# SESBOARD.net
KiCad netlist of a schematic drawn in EasyEDA
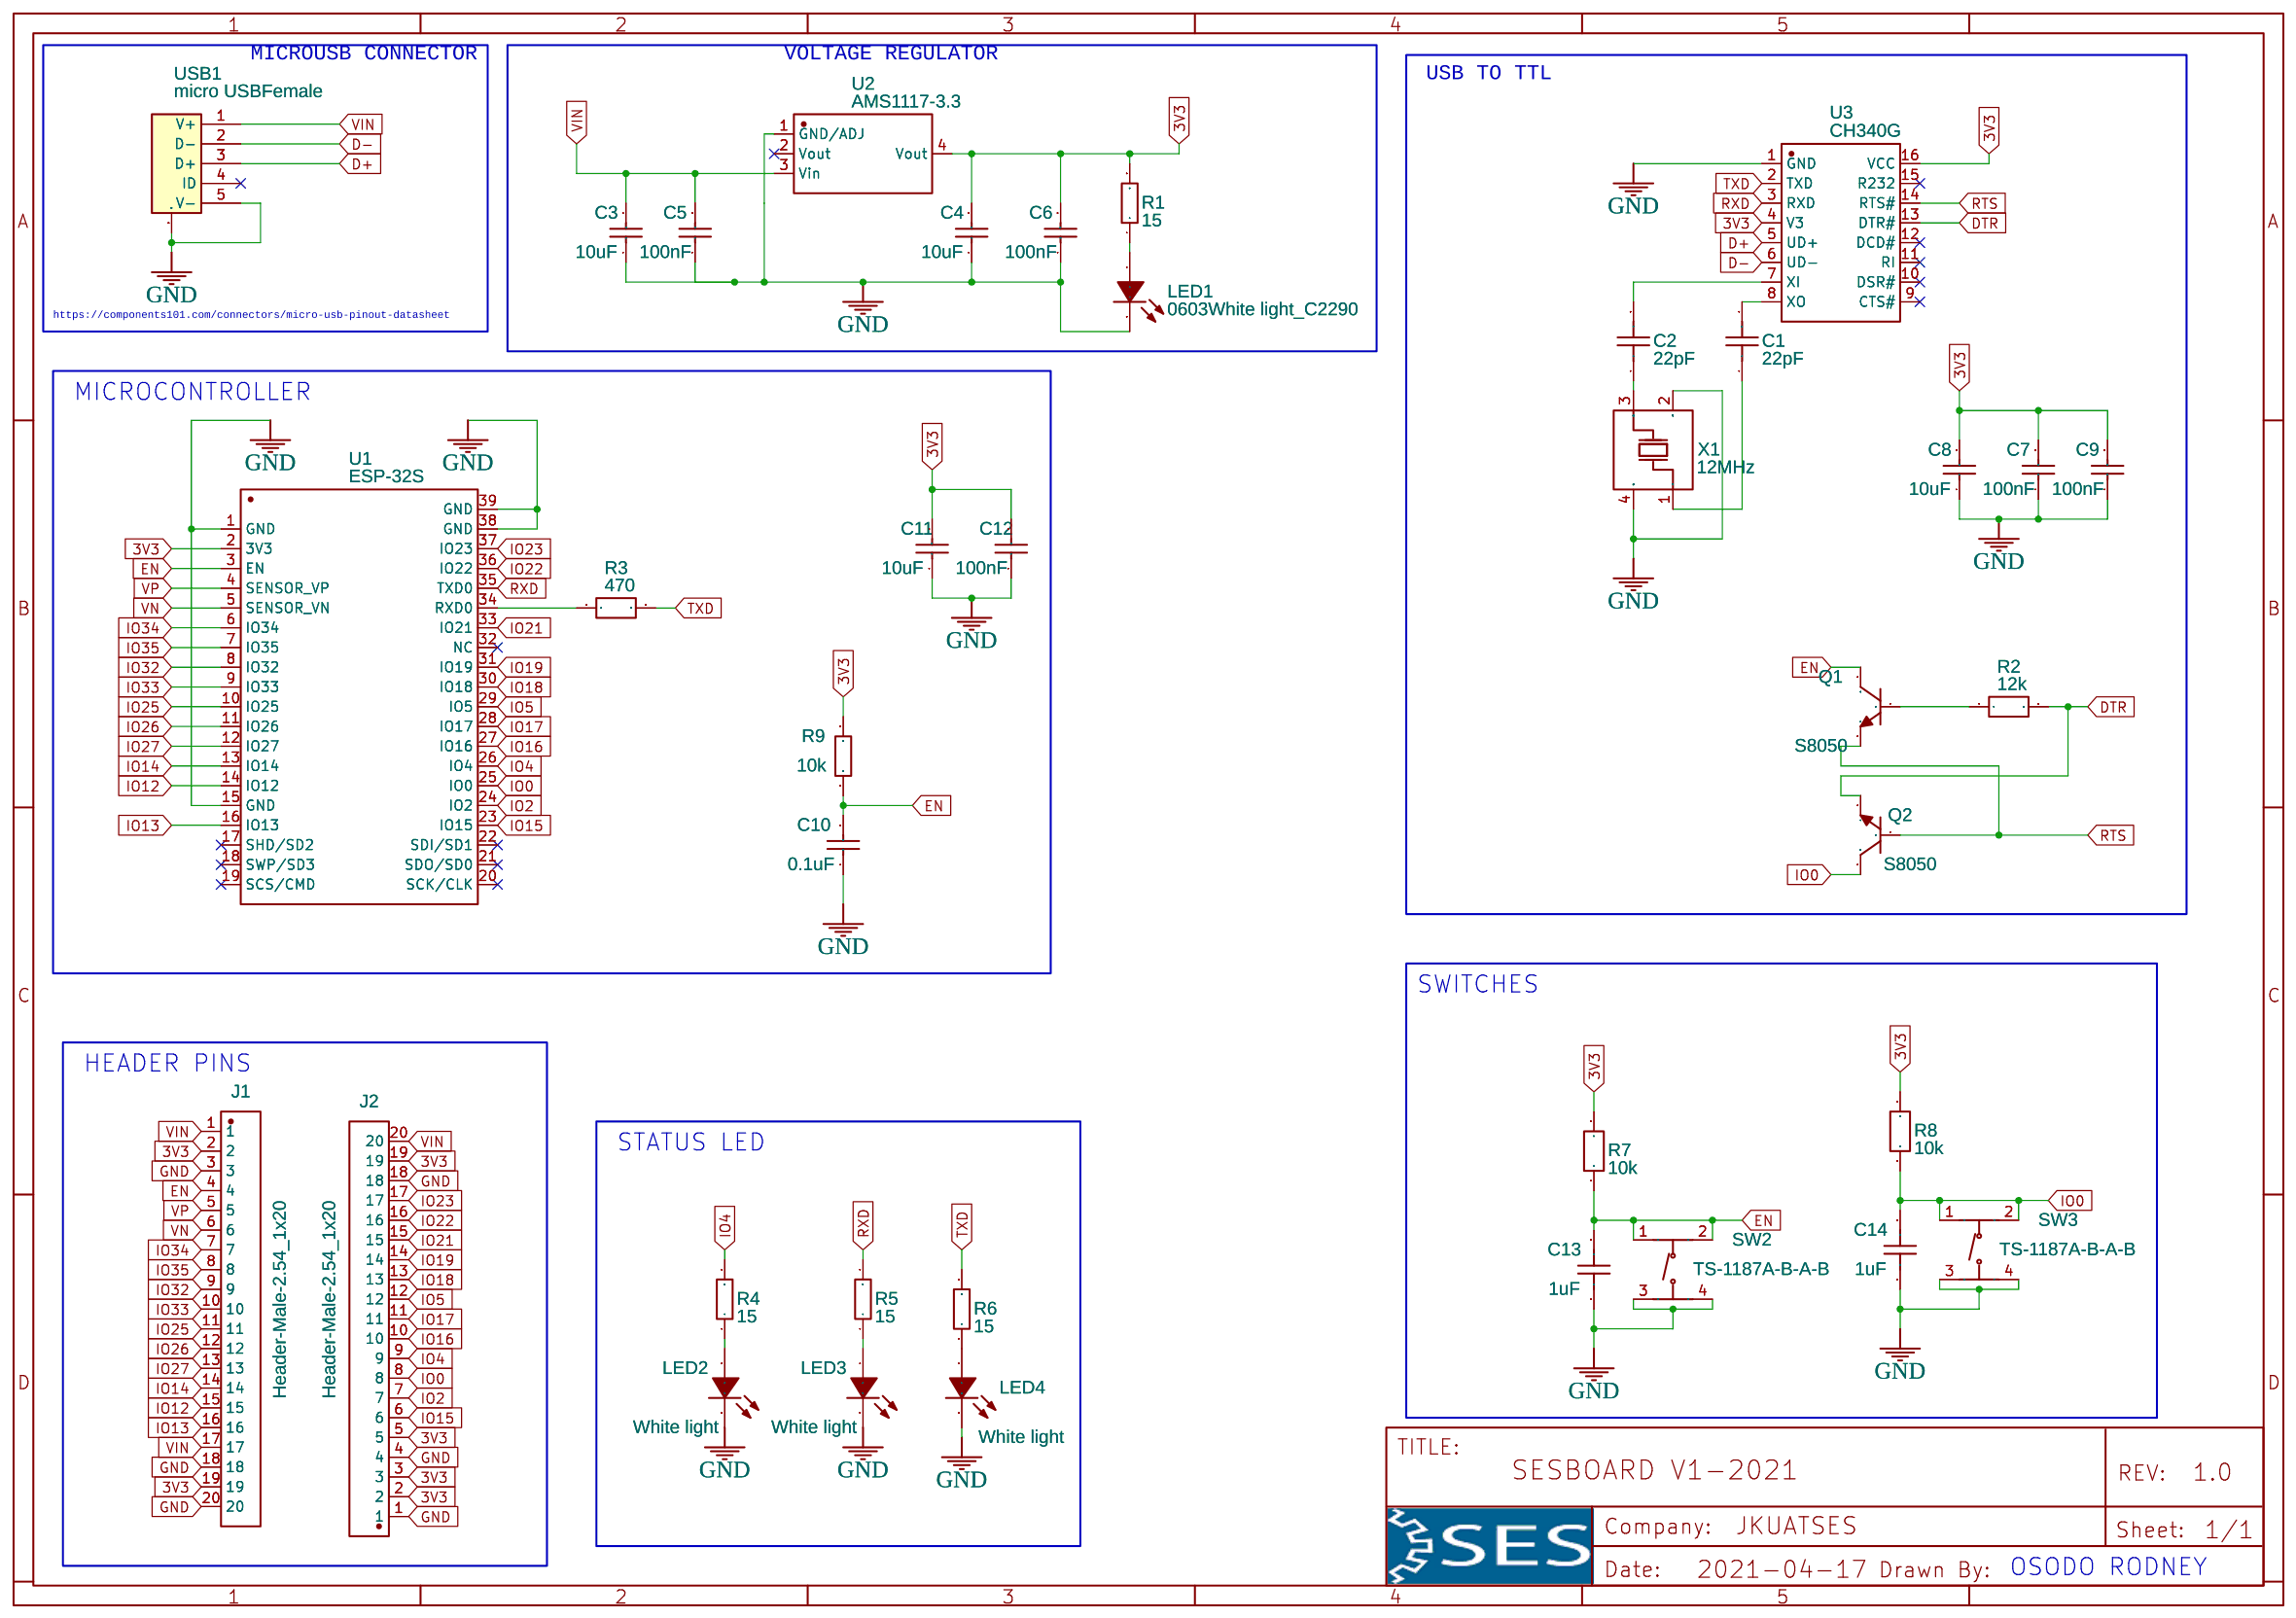
[diagram p0: schematic sheet]

(export (version "E")
  (design (tool "Eeschema 10.0.6"))
  (components
    (comp (ref "C1")
      (value "22pF")
      (fields
        (field (name "BOM_Manufacturer Part") "TCC0805COG220J500BT")
        (field (name "BOM_Supplier Part") "C376875")
      )
      (libsource (lib "") (part "TCC0805COG220J500BT"))
    )
    (comp (ref "C2")
      (value "22pF")
      (fields
        (field (name "BOM_Manufacturer Part") "TCC0805COG220J500BT")
        (field (name "BOM_Supplier Part") "C376875")
      )
      (libsource (lib "") (part "TCC0805COG220J500BT"))
    )
    (comp (ref "C3")
      (value "10uF")
      (fields
        (field (name "BOM_Manufacturer Part") "CL21A106KPFNNNE")
        (field (name "BOM_Supplier Part") "C17024")
      )
      (libsource (lib "") (part "CL21A106KPFNNNE"))
    )
    (comp (ref "C4")
      (value "10uF")
      (fields
        (field (name "BOM_Manufacturer Part") "CL21A106KPFNNNE")
        (field (name "BOM_Supplier Part") "C17024")
      )
      (libsource (lib "") (part "CL21A106KPFNNNE"))
    )
    (comp (ref "C5")
      (value "100nF")
      (fields
        (field (name "BOM_Manufacturer Part") "CL21F104ZBCNNNC")
        (field (name "BOM_Supplier Part") "C1760")
      )
      (libsource (lib "") (part "CL21F104ZBCNNNC"))
    )
    (comp (ref "C6")
      (value "100nF")
      (fields
        (field (name "BOM_Manufacturer Part") "CL21F104ZBCNNNC")
        (field (name "BOM_Supplier Part") "C1760")
      )
      (libsource (lib "") (part "CL21F104ZBCNNNC"))
    )
    (comp (ref "C7")
      (value "100nF")
      (fields
        (field (name "BOM_Manufacturer Part") "CL21F104ZBCNNNC")
        (field (name "BOM_Supplier Part") "C1760")
      )
      (libsource (lib "") (part "CL21F104ZBCNNNC"))
    )
    (comp (ref "C8")
      (value "10uF")
      (fields
        (field (name "BOM_Manufacturer Part") "CL21A106KPFNNNE")
        (field (name "BOM_Supplier Part") "C17024")
      )
      (libsource (lib "") (part "CL21A106KPFNNNE"))
    )
    (comp (ref "C9")
      (value "100nF")
      (fields
        (field (name "BOM_Manufacturer Part") "CL21F104ZBCNNNC")
        (field (name "BOM_Supplier Part") "C1760")
      )
      (libsource (lib "") (part "CL21F104ZBCNNNC"))
    )
    (comp (ref "C10")
      (value "0.1uF")
      (fields
        (field (name "BOM_Manufacturer Part") "CL21F104ZBCNNNC")
        (field (name "BOM_Supplier Part") "C1760")
      )
      (libsource (lib "") (part "CL21F104ZBCNNNC"))
    )
    (comp (ref "C11")
      (value "10uF")
      (fields
        (field (name "BOM_Manufacturer Part") "CL21A106KPFNNNE")
        (field (name "BOM_Supplier Part") "C17024")
      )
      (libsource (lib "") (part "CL21A106KPFNNNE"))
    )
    (comp (ref "C12")
      (value "100nF")
      (fields
        (field (name "BOM_Manufacturer Part") "CL21F104ZBCNNNC")
        (field (name "BOM_Supplier Part") "C1760")
      )
      (libsource (lib "") (part "CL21F104ZBCNNNC"))
    )
    (comp (ref "C13") (value "1uF") (libsource (lib "") (part "C_0603_US")))
    (comp (ref "C14") (value "1uF") (libsource (lib "") (part "C_0603_US")))
    (comp (ref "J1")
      (value "Header-Male-2.54_1x20")
      (fields
        (field (name "BOM_Manufacturer Part") "2.54mm 1*20PHeader")
        (field (name "BOM_Supplier Part") "C50981")
      )
      (libsource (lib "") (part "Header-Male-2.54_1x20_1"))
    )
    (comp (ref "J2")
      (value "Header-Male-2.54_1x20")
      (fields
        (field (name "BOM_Manufacturer Part") "2.54mm 1*20PHeader")
        (field (name "BOM_Supplier Part") "C50981")
      )
      (libsource (lib "") (part "Header-Male-2.54_1x20"))
    )
    (comp (ref "LED1")
      (value "0603White light_C2290")
      (fields
        (field (name "BOM_Manufacturer Part") "0603White light")
        (field (name "BOM_Supplier Part") "C2290")
      )
      (libsource (lib "") (part "0603White light_C2290"))
    )
    (comp (ref "LED2")
      (value "White light")
      (fields
        (field (name "BOM_Manufacturer Part") "0603White light")
        (field (name "BOM_Supplier Part") "C2290")
      )
      (libsource (lib "") (part "0603White light_C2290"))
    )
    (comp (ref "LED3")
      (value "White light")
      (fields
        (field (name "BOM_Manufacturer Part") "0603White light")
        (field (name "BOM_Supplier Part") "C2290")
      )
      (libsource (lib "") (part "0603White light_C2290"))
    )
    (comp (ref "LED4")
      (value "White light")
      (fields
        (field (name "BOM_Manufacturer Part") "0603White light")
        (field (name "BOM_Supplier Part") "C2290")
      )
      (libsource (lib "") (part "0603White light_C2290"))
    )
    (comp (ref "Q1")
      (value "S8050")
      (fields (field (name "BOM_Supplier Part") "C909746"))
      (libsource (lib "") (part "S8050"))
    )
    (comp (ref "Q2")
      (value "S8050")
      (fields (field (name "BOM_Supplier Part") "C909746"))
      (libsource (lib "") (part "S8050_1"))
    )
    (comp (ref "R1")
      (value "15")
      (fields
        (field (name "BOM_Manufacturer Part") "0603WAF150JT5E")
        (field (name "BOM_Supplier Part") "C22810")
      )
      (libsource (lib "") (part "0603WAF150JT5E"))
    )
    (comp (ref "R2") (value "12k") (libsource (lib "") (part "R_0603_EU_1")))
    (comp (ref "R3") (value "470") (libsource (lib "") (part "R_0603_EU_1")))
    (comp (ref "R4")
      (value "15")
      (fields
        (field (name "BOM_Manufacturer Part") "0603WAF150JT5E")
        (field (name "BOM_Supplier Part") "C22810")
      )
      (libsource (lib "") (part "0603WAF150JT5E"))
    )
    (comp (ref "R5")
      (value "15")
      (fields
        (field (name "BOM_Manufacturer Part") "0603WAF150JT5E")
        (field (name "BOM_Supplier Part") "C22810")
      )
      (libsource (lib "") (part "0603WAF150JT5E"))
    )
    (comp (ref "R6")
      (value "15")
      (fields
        (field (name "BOM_Manufacturer Part") "0603WAF150JT5E")
        (field (name "BOM_Supplier Part") "C22810")
      )
      (libsource (lib "") (part "0603WAF150JT5E"))
    )
    (comp (ref "R7") (value "10k") (libsource (lib "") (part "R_0603_EU")))
    (comp (ref "R8") (value "10k") (libsource (lib "") (part "R_0603_EU")))
    (comp (ref "R9")
      (value "10k")
      (fields
        (field (name "BOM_Manufacturer Part") "0603WAF150JT5E")
        (field (name "BOM_Supplier Part") "C22810")
      )
      (libsource (lib "") (part "0603WAF150JT5E"))
    )
    (comp (ref "SW2")
      (value "TS-1187A-B-A-B")
      (fields (field (name "BOM_Supplier Part") "C318884"))
      (libsource (lib "") (part "TS-1187A-B-A-B"))
    )
    (comp (ref "SW3")
      (value "TS-1187A-B-A-B")
      (fields (field (name "BOM_Supplier Part") "C318884"))
      (libsource (lib "") (part "TS-1187A-B-A-B"))
    )
    (comp (ref "U1")
      (value "ESP-32S")
      (fields (field (name "BOM_Supplier Part") "C82899"))
      (libsource (lib "") (part "ESP-32S"))
    )
    (comp (ref "U2")
      (value "AMS1117-3.3")
      (fields (field (name "BOM_Supplier Part") "C6186"))
      (libsource (lib "") (part "AMS1117-3.3"))
    )
    (comp (ref "U3")
      (value "CH340G")
      (fields (field (name "BOM_Supplier Part") "C14267"))
      (libsource (lib "") (part "CH340G"))
    )
    (comp (ref "USB1")
      (value "micro USBFemale")
      (fields (field (name "BOM_Supplier Part") "C10418"))
      (libsource (lib "") (part "micro USBFemale"))
    )
    (comp (ref "X1")
      (value "12MHz")
      (fields
        (field (name "BOM_Manufacturer Part") "X322512MSB4SI")
        (field (name "BOM_Supplier Part") "C9002")
      )
      (libsource (lib "") (part "X322512MSB4SI"))
    )
  )
  (nets
    (net (code "1") (name "3V3") (class "Default")
      (node (ref "C11") (pin "2") (pinfunction "2_2") (pintype "input"))
      (node (ref "C12") (pin "2") (pinfunction "2_2") (pintype "input"))
      (node (ref "C4") (pin "2") (pinfunction "2_2") (pintype "input"))
      (node (ref "C6") (pin "2") (pinfunction "2_2") (pintype "input"))
      (node (ref "C7") (pin "2") (pinfunction "2_2") (pintype "input"))
      (node (ref "C8") (pin "2") (pinfunction "2_2") (pintype "input"))
      (node (ref "C9") (pin "2") (pinfunction "2_2") (pintype "input"))
      (node (ref "J1") (pin "19") (pinfunction "19_19") (pintype "unspecified"))
      (node (ref "J1") (pin "2") (pinfunction "2_2") (pintype "unspecified"))
      (node (ref "J2") (pin "19") (pinfunction "19_19") (pintype "unspecified"))
      (node (ref "J2") (pin "2") (pinfunction "2_2") (pintype "unspecified"))
      (node (ref "J2") (pin "3") (pinfunction "3_3") (pintype "unspecified"))
      (node (ref "J2") (pin "5") (pinfunction "5_5") (pintype "unspecified"))
      (node (ref "R1") (pin "2") (pinfunction "2_2") (pintype "input"))
      (node (ref "R7") (pin "2") (pinfunction "2_2") (pintype "unspecified"))
      (node (ref "R8") (pin "2") (pinfunction "2_2") (pintype "unspecified"))
      (node (ref "R9") (pin "2") (pinfunction "2_2") (pintype "input"))
      (node (ref "U1") (pin "2") (pinfunction "3V3_2") (pintype "unspecified"))
      (node (ref "U2") (pin "4") (pinfunction "Vout_4") (pintype "unspecified"))
      (node (ref "U3") (pin "16") (pinfunction "VCC_16") (pintype "unspecified"))
      (node (ref "U3") (pin "4") (pinfunction "V3_4") (pintype "unspecified"))
    )
    (net (code "2") (name "D+") (class "Default")
      (node (ref "U3") (pin "5") (pinfunction "UD+_5") (pintype "unspecified"))
      (node (ref "USB1") (pin "3") (pinfunction "D+_3") (pintype "unspecified"))
    )
    (net (code "3") (name "D-") (class "Default")
      (node (ref "U3") (pin "6") (pinfunction "UD-_6") (pintype "unspecified"))
      (node (ref "USB1") (pin "2") (pinfunction "D-_2") (pintype "unspecified"))
    )
    (net (code "4") (name "DTR") (class "Default")
      (node (ref "Q2") (pin "2") (pinfunction "E_2") (pintype "input"))
      (node (ref "R2") (pin "2") (pinfunction "2_2") (pintype "unspecified"))
      (node (ref "U3") (pin "13") (pinfunction "DTR#_13") (pintype "unspecified"))
    )
    (net (code "5") (name "EN") (class "Default")
      (node (ref "C10") (pin "2") (pinfunction "2_2") (pintype "input"))
      (node (ref "C13") (pin "2") (pinfunction "2_2") (pintype "unspecified"))
      (node (ref "J1") (pin "4") (pinfunction "4_4") (pintype "unspecified"))
      (node (ref "Q1") (pin "3") (pinfunction "C_3") (pintype "input"))
      (node (ref "R7") (pin "1") (pinfunction "1_1") (pintype "unspecified"))
      (node (ref "R9") (pin "1") (pinfunction "1_1") (pintype "input"))
      (node (ref "SW2") (pin "1") (pinfunction "A_1") (pintype "unspecified"))
      (node (ref "SW2") (pin "2") (pinfunction "B_2") (pintype "unspecified"))
      (node (ref "U1") (pin "3") (pinfunction "EN_3") (pintype "unspecified"))
    )
    (net (code "6") (name "GND") (class "Default")
      (node (ref "C10") (pin "1") (pinfunction "1_1") (pintype "input"))
      (node (ref "C11") (pin "1") (pinfunction "1_1") (pintype "input"))
      (node (ref "C12") (pin "1") (pinfunction "1_1") (pintype "input"))
      (node (ref "C13") (pin "1") (pinfunction "1_1") (pintype "unspecified"))
      (node (ref "C14") (pin "1") (pinfunction "1_1") (pintype "unspecified"))
      (node (ref "C3") (pin "1") (pinfunction "1_1") (pintype "input"))
      (node (ref "C4") (pin "1") (pinfunction "1_1") (pintype "input"))
      (node (ref "C5") (pin "1") (pinfunction "1_1") (pintype "input"))
      (node (ref "C6") (pin "1") (pinfunction "1_1") (pintype "input"))
      (node (ref "C7") (pin "1") (pinfunction "1_1") (pintype "input"))
      (node (ref "C8") (pin "1") (pinfunction "1_1") (pintype "input"))
      (node (ref "C9") (pin "1") (pinfunction "1_1") (pintype "input"))
      (node (ref "J1") (pin "18") (pinfunction "18_18") (pintype "unspecified"))
      (node (ref "J1") (pin "20") (pinfunction "20_20") (pintype "unspecified"))
      (node (ref "J1") (pin "3") (pinfunction "3_3") (pintype "unspecified"))
      (node (ref "J2") (pin "1") (pinfunction "1_1") (pintype "unspecified"))
      (node (ref "J2") (pin "18") (pinfunction "18_18") (pintype "unspecified"))
      (node (ref "J2") (pin "4") (pinfunction "4_4") (pintype "unspecified"))
      (node (ref "LED1") (pin "2") (pinfunction "K_2") (pintype "unspecified"))
      (node (ref "LED2") (pin "2") (pinfunction "K_2") (pintype "unspecified"))
      (node (ref "LED3") (pin "2") (pinfunction "K_2") (pintype "unspecified"))
      (node (ref "LED4") (pin "2") (pinfunction "K_2") (pintype "unspecified"))
      (node (ref "SW2") (pin "3") (pinfunction "C_3") (pintype "unspecified"))
      (node (ref "SW2") (pin "4") (pinfunction "D_4") (pintype "unspecified"))
      (node (ref "SW3") (pin "3") (pinfunction "C_3") (pintype "unspecified"))
      (node (ref "SW3") (pin "4") (pinfunction "D_4") (pintype "unspecified"))
      (node (ref "U1") (pin "1") (pinfunction "GND_1") (pintype "unspecified"))
      (node (ref "U1") (pin "15") (pinfunction "GND_15") (pintype "unspecified"))
      (node (ref "U1") (pin "38") (pinfunction "GND_38") (pintype "unspecified"))
      (node (ref "U1") (pin "39") (pinfunction "GND_39") (pintype "unspecified"))
      (node (ref "U2") (pin "1") (pinfunction "GND/ADJ_1") (pintype "unspecified"))
      (node (ref "U3") (pin "1") (pinfunction "GND_1") (pintype "unspecified"))
      (node (ref "USB1") (pin "0") (pinfunction "MTN_0") (pintype "input"))
      (node (ref "USB1") (pin "5") (pinfunction "V-_5") (pintype "unspecified"))
      (node (ref "X1") (pin "2") (pinfunction "GND_2") (pintype "unspecified"))
      (node (ref "X1") (pin "4") (pinfunction "GND_4") (pintype "unspecified"))
    )
    (net (code "7") (name "IO0") (class "Default")
      (node (ref "C14") (pin "2") (pinfunction "2_2") (pintype "unspecified"))
      (node (ref "J2") (pin "8") (pinfunction "8_8") (pintype "unspecified"))
      (node (ref "Q2") (pin "3") (pinfunction "C_3") (pintype "input"))
      (node (ref "R8") (pin "1") (pinfunction "1_1") (pintype "unspecified"))
      (node (ref "SW3") (pin "1") (pinfunction "A_1") (pintype "unspecified"))
      (node (ref "SW3") (pin "2") (pinfunction "B_2") (pintype "unspecified"))
      (node (ref "U1") (pin "25") (pinfunction "IO0_25") (pintype "unspecified"))
    )
    (net (code "8") (name "IO2") (class "Default")
      (node (ref "J2") (pin "7") (pinfunction "7_7") (pintype "unspecified"))
      (node (ref "U1") (pin "24") (pinfunction "IO2_24") (pintype "unspecified"))
    )
    (net (code "9") (name "IO4") (class "Default")
      (node (ref "J2") (pin "9") (pinfunction "9_9") (pintype "unspecified"))
      (node (ref "R4") (pin "2") (pinfunction "2_2") (pintype "input"))
      (node (ref "U1") (pin "26") (pinfunction "IO4_26") (pintype "unspecified"))
    )
    (net (code "10") (name "IO5") (class "Default")
      (node (ref "J2") (pin "12") (pinfunction "12_12") (pintype "unspecified"))
      (node (ref "U1") (pin "29") (pinfunction "IO5_29") (pintype "unspecified"))
    )
    (net (code "11") (name "IO12") (class "Default")
      (node (ref "J1") (pin "15") (pinfunction "15_15") (pintype "unspecified"))
      (node (ref "U1") (pin "14") (pinfunction "IO12_14") (pintype "unspecified"))
    )
    (net (code "12") (name "IO13") (class "Default")
      (node (ref "J1") (pin "16") (pinfunction "16_16") (pintype "unspecified"))
      (node (ref "U1") (pin "16") (pinfunction "IO13_16") (pintype "unspecified"))
    )
    (net (code "13") (name "IO14") (class "Default")
      (node (ref "J1") (pin "14") (pinfunction "14_14") (pintype "unspecified"))
      (node (ref "U1") (pin "13") (pinfunction "IO14_13") (pintype "unspecified"))
    )
    (net (code "14") (name "IO15") (class "Default")
      (node (ref "J2") (pin "6") (pinfunction "6_6") (pintype "unspecified"))
      (node (ref "U1") (pin "23") (pinfunction "IO15_23") (pintype "unspecified"))
    )
    (net (code "15") (name "IO16") (class "Default")
      (node (ref "J2") (pin "10") (pinfunction "10_10") (pintype "unspecified"))
      (node (ref "U1") (pin "27") (pinfunction "IO16_27") (pintype "unspecified"))
    )
    (net (code "16") (name "IO17") (class "Default")
      (node (ref "J2") (pin "11") (pinfunction "11_11") (pintype "unspecified"))
      (node (ref "U1") (pin "28") (pinfunction "IO17_28") (pintype "unspecified"))
    )
    (net (code "17") (name "IO18") (class "Default")
      (node (ref "J2") (pin "13") (pinfunction "13_13") (pintype "unspecified"))
      (node (ref "U1") (pin "30") (pinfunction "IO18_30") (pintype "unspecified"))
    )
    (net (code "18") (name "IO19") (class "Default")
      (node (ref "J2") (pin "14") (pinfunction "14_14") (pintype "unspecified"))
      (node (ref "U1") (pin "31") (pinfunction "IO19_31") (pintype "unspecified"))
    )
    (net (code "19") (name "IO21") (class "Default")
      (node (ref "J2") (pin "15") (pinfunction "15_15") (pintype "unspecified"))
      (node (ref "U1") (pin "33") (pinfunction "IO21_33") (pintype "unspecified"))
    )
    (net (code "20") (name "IO22") (class "Default")
      (node (ref "J2") (pin "16") (pinfunction "16_16") (pintype "unspecified"))
      (node (ref "U1") (pin "36") (pinfunction "IO22_36") (pintype "unspecified"))
    )
    (net (code "21") (name "IO23") (class "Default")
      (node (ref "J2") (pin "17") (pinfunction "17_17") (pintype "unspecified"))
      (node (ref "U1") (pin "37") (pinfunction "IO23_37") (pintype "unspecified"))
    )
    (net (code "22") (name "IO25") (class "Default")
      (node (ref "J1") (pin "11") (pinfunction "11_11") (pintype "unspecified"))
      (node (ref "U1") (pin "10") (pinfunction "IO25_10") (pintype "unspecified"))
    )
    (net (code "23") (name "IO26") (class "Default")
      (node (ref "J1") (pin "12") (pinfunction "12_12") (pintype "unspecified"))
      (node (ref "U1") (pin "11") (pinfunction "IO26_11") (pintype "unspecified"))
    )
    (net (code "24") (name "IO27") (class "Default")
      (node (ref "J1") (pin "13") (pinfunction "13_13") (pintype "unspecified"))
      (node (ref "U1") (pin "12") (pinfunction "IO27_12") (pintype "unspecified"))
    )
    (net (code "25") (name "IO32") (class "Default")
      (node (ref "J1") (pin "9") (pinfunction "9_9") (pintype "unspecified"))
      (node (ref "U1") (pin "8") (pinfunction "IO32_8") (pintype "unspecified"))
    )
    (net (code "26") (name "IO33") (class "Default")
      (node (ref "J1") (pin "10") (pinfunction "10_10") (pintype "unspecified"))
      (node (ref "U1") (pin "9") (pinfunction "IO33_9") (pintype "unspecified"))
    )
    (net (code "27") (name "IO34") (class "Default")
      (node (ref "J1") (pin "7") (pinfunction "7_7") (pintype "unspecified"))
      (node (ref "U1") (pin "6") (pinfunction "IO34_6") (pintype "unspecified"))
    )
    (net (code "28") (name "IO35") (class "Default")
      (node (ref "J1") (pin "8") (pinfunction "8_8") (pintype "unspecified"))
      (node (ref "U1") (pin "7") (pinfunction "IO35_7") (pintype "unspecified"))
    )
    (net (code "29") (name "Net-(LED1-A)") (class "Default")
      (node (ref "LED1") (pin "1") (pinfunction "A_1") (pintype "unspecified"))
      (node (ref "R1") (pin "1") (pinfunction "1_1") (pintype "input"))
    )
    (net (code "30") (name "Net-(LED2-A)") (class "Default")
      (node (ref "LED2") (pin "1") (pinfunction "A_1") (pintype "unspecified"))
      (node (ref "R4") (pin "1") (pinfunction "1_1") (pintype "input"))
    )
    (net (code "31") (name "Net-(LED3-A)") (class "Default")
      (node (ref "LED3") (pin "1") (pinfunction "A_1") (pintype "unspecified"))
      (node (ref "R5") (pin "1") (pinfunction "1_1") (pintype "input"))
    )
    (net (code "32") (name "Net-(LED4-A)") (class "Default")
      (node (ref "LED4") (pin "1") (pinfunction "A_1") (pintype "unspecified"))
      (node (ref "R6") (pin "1") (pinfunction "1_1") (pintype "input"))
    )
    (net (code "33") (name "Net-(Q1-B)") (class "Default")
      (node (ref "Q1") (pin "1") (pinfunction "B_1") (pintype "input"))
      (node (ref "R2") (pin "1") (pinfunction "1_1") (pintype "unspecified"))
    )
    (net (code "34") (name "Net-(U1-RXD0)") (class "Default")
      (node (ref "R3") (pin "1") (pinfunction "1_1") (pintype "unspecified"))
      (node (ref "U1") (pin "34") (pinfunction "RXD0_34") (pintype "unspecified"))
    )
    (net (code "35") (name "Net-(U3-XI)") (class "Default")
      (node (ref "C2") (pin "2") (pinfunction "2_2") (pintype "unspecified"))
      (node (ref "U3") (pin "7") (pinfunction "XI_7") (pintype "unspecified"))
    )
    (net (code "36") (name "Net-(U3-XO)") (class "Default")
      (node (ref "C1") (pin "2") (pinfunction "2_2") (pintype "unspecified"))
      (node (ref "U3") (pin "8") (pinfunction "XO_8") (pintype "unspecified"))
    )
    (net (code "37") (name "Net-(X1-OSC1)") (class "Default")
      (node (ref "C1") (pin "1") (pinfunction "1_1") (pintype "unspecified"))
      (node (ref "X1") (pin "1") (pinfunction "OSC1_1") (pintype "unspecified"))
    )
    (net (code "38") (name "Net-(X1-OSC2)") (class "Default")
      (node (ref "C2") (pin "1") (pinfunction "1_1") (pintype "unspecified"))
      (node (ref "X1") (pin "3") (pinfunction "OSC2_3") (pintype "unspecified"))
    )
    (net (code "39") (name "RTS") (class "Default")
      (node (ref "Q1") (pin "2") (pinfunction "E_2") (pintype "input"))
      (node (ref "Q2") (pin "1") (pinfunction "B_1") (pintype "input"))
      (node (ref "U3") (pin "14") (pinfunction "RTS#_14") (pintype "unspecified"))
    )
    (net (code "40") (name "RXD") (class "Default")
      (node (ref "R5") (pin "2") (pinfunction "2_2") (pintype "input"))
      (node (ref "U1") (pin "35") (pinfunction "TXD0_35") (pintype "unspecified"))
      (node (ref "U3") (pin "3") (pinfunction "RXD_3") (pintype "unspecified"))
    )
    (net (code "41") (name "TXD") (class "Default")
      (node (ref "R3") (pin "2") (pinfunction "2_2") (pintype "unspecified"))
      (node (ref "R6") (pin "2") (pinfunction "2_2") (pintype "input"))
      (node (ref "U3") (pin "2") (pinfunction "TXD_2") (pintype "unspecified"))
    )
    (net (code "42") (name "VIN") (class "Default")
      (node (ref "C3") (pin "2") (pinfunction "2_2") (pintype "input"))
      (node (ref "C5") (pin "2") (pinfunction "2_2") (pintype "input"))
      (node (ref "J1") (pin "1") (pinfunction "1_1") (pintype "unspecified"))
      (node (ref "J1") (pin "17") (pinfunction "17_17") (pintype "unspecified"))
      (node (ref "J2") (pin "20") (pinfunction "20_20") (pintype "unspecified"))
      (node (ref "U2") (pin "3") (pinfunction "Vin_3") (pintype "unspecified"))
      (node (ref "USB1") (pin "1") (pinfunction "V+_1") (pintype "unspecified"))
    )
    (net (code "43") (name "VN") (class "Default")
      (node (ref "J1") (pin "6") (pinfunction "6_6") (pintype "unspecified"))
      (node (ref "U1") (pin "5") (pinfunction "SENSOR_VN_5") (pintype "unspecified"))
    )
    (net (code "44") (name "VP") (class "Default")
      (node (ref "J1") (pin "5") (pinfunction "5_5") (pintype "unspecified"))
      (node (ref "U1") (pin "4") (pinfunction "SENSOR_VP_4") (pintype "unspecified"))
    )
    (net (code "45") (name "unconnected-(U1-NC-Pad32)") (class "Default")
      (node (ref "U1") (pin "32") (pinfunction "NC_32") (pintype "unspecified+no_connect"))
    )
    (net (code "46") (name "unconnected-(U1-SCK{slash}CLK-Pad20)") (class "Default")
      (node (ref "U1") (pin "20") (pinfunction "SCK/CLK_20") (pintype "unspecified+no_connect"))
    )
    (net (code "47") (name "unconnected-(U1-SCS{slash}CMD-Pad19)") (class "Default")
      (node (ref "U1") (pin "19") (pinfunction "SCS/CMD_19") (pintype "unspecified+no_connect"))
    )
    (net (code "48") (name "unconnected-(U1-SDI{slash}SD1-Pad22)") (class "Default")
      (node (ref "U1") (pin "22") (pinfunction "SDI/SD1_22") (pintype "unspecified+no_connect"))
    )
    (net (code "49") (name "unconnected-(U1-SDO{slash}SD0-Pad21)") (class "Default")
      (node (ref "U1") (pin "21") (pinfunction "SDO/SD0_21") (pintype "unspecified+no_connect"))
    )
    (net (code "50") (name "unconnected-(U1-SHD{slash}SD2-Pad17)") (class "Default")
      (node (ref "U1") (pin "17") (pinfunction "SHD/SD2_17") (pintype "unspecified+no_connect"))
    )
    (net (code "51") (name "unconnected-(U1-SWP{slash}SD3-Pad18)") (class "Default")
      (node (ref "U1") (pin "18") (pinfunction "SWP/SD3_18") (pintype "unspecified+no_connect"))
    )
    (net (code "52") (name "unconnected-(U2-Vout-Pad2)") (class "Default")
      (node (ref "U2") (pin "2") (pinfunction "Vout_2") (pintype "unspecified+no_connect"))
    )
    (net (code "53") (name "unconnected-(U3-CTS#-Pad9)") (class "Default")
      (node (ref "U3") (pin "9") (pinfunction "CTS#_9") (pintype "unspecified+no_connect"))
    )
    (net (code "54") (name "unconnected-(U3-DCD#-Pad12)") (class "Default")
      (node (ref "U3") (pin "12") (pinfunction "DCD#_12") (pintype "unspecified+no_connect"))
    )
    (net (code "55") (name "unconnected-(U3-DSR#-Pad10)") (class "Default")
      (node (ref "U3") (pin "10") (pinfunction "DSR#_10") (pintype "unspecified+no_connect"))
    )
    (net (code "56") (name "unconnected-(U3-R232-Pad15)") (class "Default")
      (node (ref "U3") (pin "15") (pinfunction "R232_15") (pintype "unspecified+no_connect"))
    )
    (net (code "57") (name "unconnected-(U3-RI-Pad11)") (class "Default")
      (node (ref "U3") (pin "11") (pinfunction "RI_11") (pintype "unspecified+no_connect"))
    )
    (net (code "58") (name "unconnected-(USB1-ID-Pad4)") (class "Default")
      (node (ref "USB1") (pin "4") (pinfunction "ID_4") (pintype "unspecified+no_connect"))
    )
  )
)
